# SCH_Test_2024-05-07.net
KiCad netlist of a schematic drawn in EasyEDA
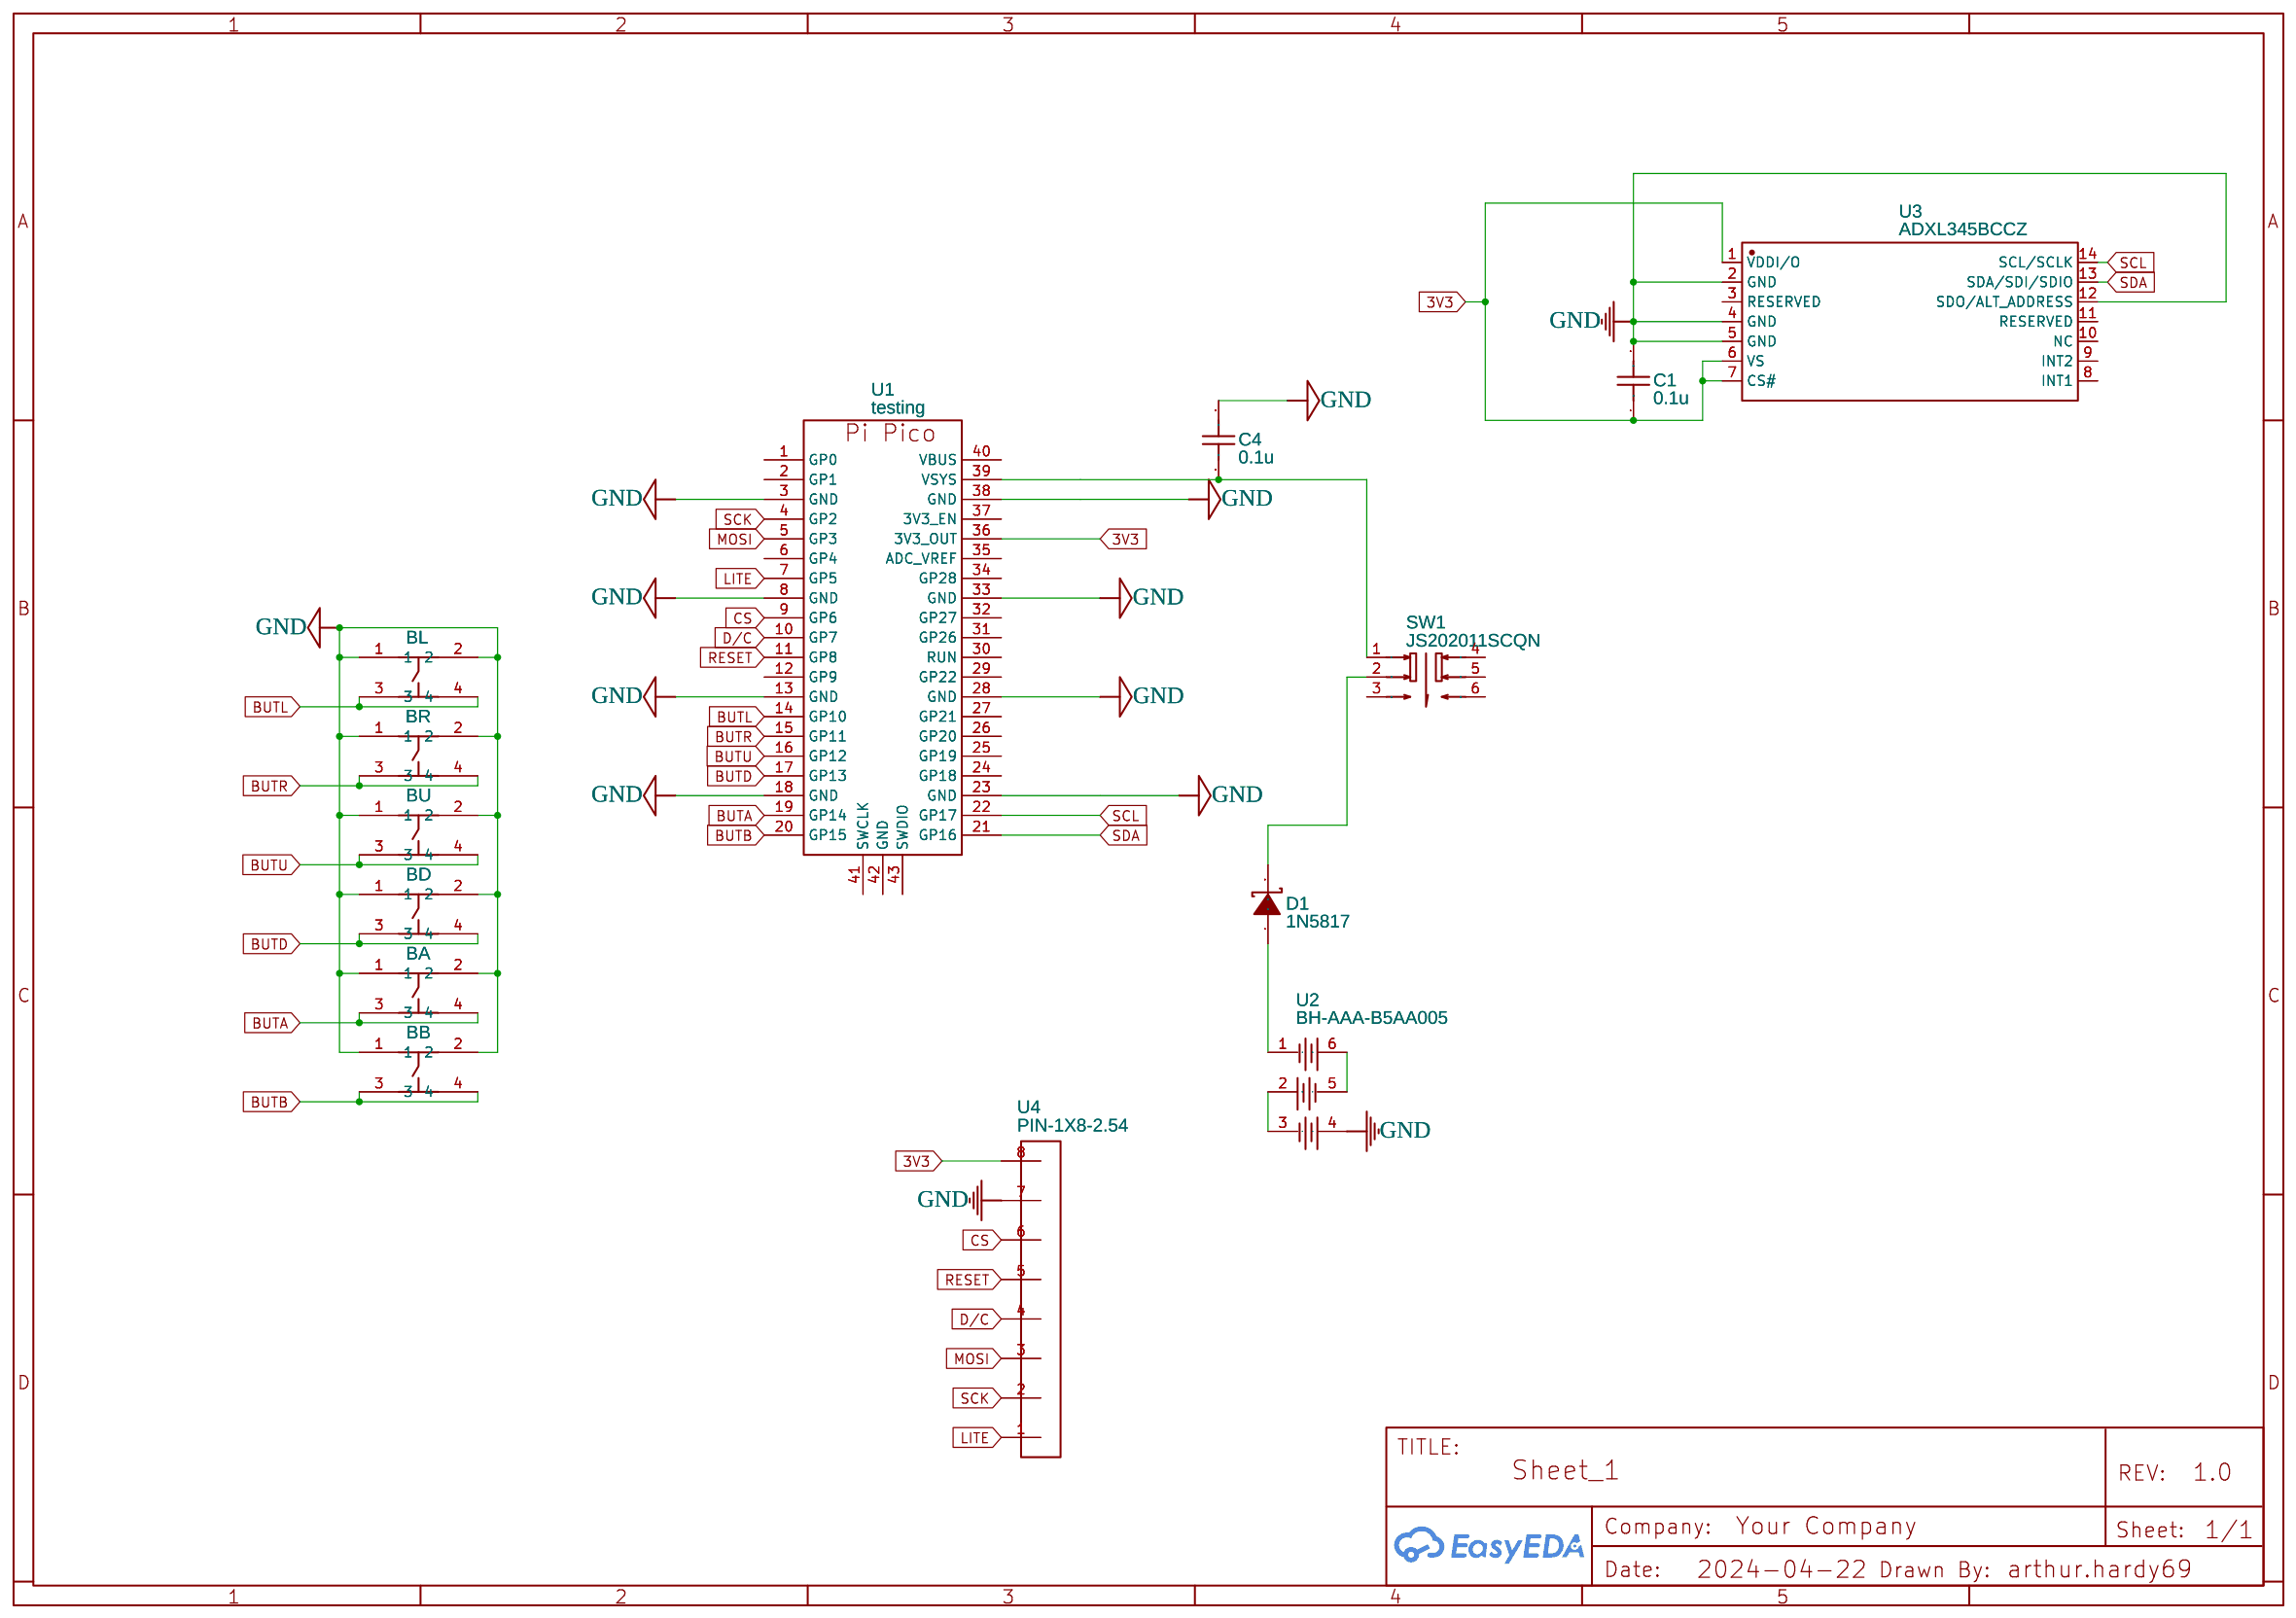
[diagram p0: schematic sheet]

(export (version "E")
  (design (tool "Eeschema 10.0.6"))
  (components
    (comp (ref "BA")
      (value "A")
      (fields (field (name "Manufacturer Part") "3101") (field (name "Manufacturer") "Adafruit"))
      (libsource (lib "") (part "Soft Tactile Button 8x8 (Adafruit 3101)_3"))
    )
    (comp (ref "BB")
      (value "B")
      (fields (field (name "Manufacturer Part") "3101") (field (name "Manufacturer") "Adafruit"))
      (libsource (lib "") (part "Soft Tactile Button 8x8 (Adafruit 3101)"))
    )
    (comp (ref "BD")
      (value "Down")
      (fields (field (name "Manufacturer Part") "3101") (field (name "Manufacturer") "Adafruit"))
      (libsource (lib "") (part "Soft Tactile Button 8x8 (Adafruit 3101)_2"))
    )
    (comp (ref "BL")
      (value "Left")
      (fields (field (name "Manufacturer Part") "3101") (field (name "Manufacturer") "Adafruit"))
      (libsource (lib "") (part "Soft Tactile Button 8x8 (Adafruit 3101)_1"))
    )
    (comp (ref "BR")
      (value "Right")
      (fields (field (name "Manufacturer Part") "3101") (field (name "Manufacturer") "Adafruit"))
      (libsource (lib "") (part "Soft Tactile Button 8x8 (Adafruit 3101)_5"))
    )
    (comp (ref "BU")
      (value "Up")
      (fields (field (name "Manufacturer Part") "3101") (field (name "Manufacturer") "Adafruit"))
      (libsource (lib "") (part "Soft Tactile Button 8x8 (Adafruit 3101)_4"))
    )
    (comp (ref "C1") (value "0.1u") (libsource (lib "") (part "C_0603_US")))
    (comp (ref "C4") (value "0.1u") (libsource (lib "") (part "C_0603_US")))
    (comp (ref "D1")
      (value "1N5817")
      (fields (field (name "Manufacturer") "MDD"))
      (libsource (lib "") (part "1N5817"))
    )
    (comp (ref "SW1")
      (value "JS202011SCQN")
      (fields (field (name "Manufacturer") "C&K"))
      (libsource (lib "") (part "JS202011SCQN"))
    )
    (comp (ref "U1")
      (value "testing")
      (fields
        (field (name "Manufacturer Part") "Pi Pico")
        (field (name "Manufacturer") "Raspberry Pi Foundation")
      )
      (libsource (lib "") (part "testing"))
    )
    (comp (ref "U2")
      (value "BH-AAA-B5AA005")
      (fields (field (name "Manufacturer") "MYOUNG(美阳)"))
      (libsource (lib "") (part "BH-AAA-B5AA005"))
    )
    (comp (ref "U3")
      (value "ADXL345BCCZ")
      (fields (field (name "Manufacturer") "ADI(亚德诺)"))
      (libsource (lib "") (part "ADXL345BCCZ"))
    )
    (comp (ref "U4") (value "PIN-1X8-2.54") (libsource (lib "") (part "PIN-1X8-2.54")))
  )
  (nets
    (net (code "1") (name "3V3") (class "Default")
      (node (ref "C1") (pin "1") (pinfunction "1_1") (pintype "unspecified"))
      (node (ref "U1") (pin "36") (pinfunction "3V3_OUT_36") (pintype "unspecified"))
      (node (ref "U3") (pin "1") (pinfunction "VDDI/O_1") (pintype "unspecified"))
      (node (ref "U3") (pin "6") (pinfunction "VS_6") (pintype "unspecified"))
      (node (ref "U3") (pin "7") (pinfunction "CS#_7") (pintype "unspecified"))
      (node (ref "U4") (pin "8") (pintype "unspecified"))
    )
    (net (code "2") (name "BUTA") (class "Default")
      (node (ref "BA") (pin "3") (pinfunction "3_3") (pintype "unspecified"))
      (node (ref "BA") (pin "4") (pinfunction "4_4") (pintype "unspecified"))
      (node (ref "U1") (pin "19") (pinfunction "GP14_19") (pintype "unspecified"))
    )
    (net (code "3") (name "BUTB") (class "Default")
      (node (ref "BB") (pin "3") (pinfunction "3_3") (pintype "unspecified"))
      (node (ref "BB") (pin "4") (pinfunction "4_4") (pintype "unspecified"))
      (node (ref "U1") (pin "20") (pinfunction "GP15_20") (pintype "unspecified"))
    )
    (net (code "4") (name "BUTD") (class "Default")
      (node (ref "BD") (pin "3") (pinfunction "3_3") (pintype "unspecified"))
      (node (ref "BD") (pin "4") (pinfunction "4_4") (pintype "unspecified"))
      (node (ref "U1") (pin "17") (pinfunction "GP13_17") (pintype "unspecified"))
    )
    (net (code "5") (name "BUTL") (class "Default")
      (node (ref "BL") (pin "3") (pinfunction "3_3") (pintype "unspecified"))
      (node (ref "BL") (pin "4") (pinfunction "4_4") (pintype "unspecified"))
      (node (ref "U1") (pin "14") (pinfunction "GP10_14") (pintype "unspecified"))
    )
    (net (code "6") (name "BUTR") (class "Default")
      (node (ref "BR") (pin "3") (pinfunction "3_3") (pintype "unspecified"))
      (node (ref "BR") (pin "4") (pinfunction "4_4") (pintype "unspecified"))
      (node (ref "U1") (pin "15") (pinfunction "GP11_15") (pintype "unspecified"))
    )
    (net (code "7") (name "BUTU") (class "Default")
      (node (ref "BU") (pin "3") (pinfunction "3_3") (pintype "unspecified"))
      (node (ref "BU") (pin "4") (pinfunction "4_4") (pintype "unspecified"))
      (node (ref "U1") (pin "16") (pinfunction "GP12_16") (pintype "unspecified"))
    )
    (net (code "8") (name "CS") (class "Default")
      (node (ref "U1") (pin "9") (pinfunction "GP6_9") (pintype "unspecified"))
      (node (ref "U4") (pin "6") (pintype "unspecified"))
    )
    (net (code "9") (name "D{slash}C") (class "Default")
      (node (ref "U1") (pin "10") (pinfunction "GP7_10") (pintype "unspecified"))
      (node (ref "U4") (pin "4") (pintype "unspecified"))
    )
    (net (code "10") (name "GND") (class "Default")
      (node (ref "BA") (pin "1") (pinfunction "1_1") (pintype "unspecified"))
      (node (ref "BA") (pin "2") (pinfunction "2_2") (pintype "unspecified"))
      (node (ref "BB") (pin "1") (pinfunction "1_1") (pintype "unspecified"))
      (node (ref "BB") (pin "2") (pinfunction "2_2") (pintype "unspecified"))
      (node (ref "BD") (pin "1") (pinfunction "1_1") (pintype "unspecified"))
      (node (ref "BD") (pin "2") (pinfunction "2_2") (pintype "unspecified"))
      (node (ref "BL") (pin "1") (pinfunction "1_1") (pintype "unspecified"))
      (node (ref "BL") (pin "2") (pinfunction "2_2") (pintype "unspecified"))
      (node (ref "BR") (pin "1") (pinfunction "1_1") (pintype "unspecified"))
      (node (ref "BR") (pin "2") (pinfunction "2_2") (pintype "unspecified"))
      (node (ref "BU") (pin "1") (pinfunction "1_1") (pintype "unspecified"))
      (node (ref "BU") (pin "2") (pinfunction "2_2") (pintype "unspecified"))
      (node (ref "C1") (pin "2") (pinfunction "2_2") (pintype "unspecified"))
      (node (ref "C4") (pin "2") (pinfunction "2_2") (pintype "unspecified"))
      (node (ref "U1") (pin "13") (pinfunction "GND_13") (pintype "unspecified"))
      (node (ref "U1") (pin "18") (pinfunction "GND_18") (pintype "unspecified"))
      (node (ref "U1") (pin "23") (pinfunction "GND_23") (pintype "unspecified"))
      (node (ref "U1") (pin "28") (pinfunction "GND_28") (pintype "unspecified"))
      (node (ref "U1") (pin "3") (pinfunction "GND_3") (pintype "unspecified"))
      (node (ref "U1") (pin "33") (pinfunction "GND_33") (pintype "unspecified"))
      (node (ref "U1") (pin "38") (pinfunction "GND_38") (pintype "unspecified"))
      (node (ref "U1") (pin "8") (pinfunction "GND_8") (pintype "unspecified"))
      (node (ref "U2") (pin "4") (pinfunction "+_4") (pintype "input"))
      (node (ref "U3") (pin "12") (pinfunction "SDO/ALT_ADDRESS_12") (pintype "unspecified"))
      (node (ref "U3") (pin "2") (pinfunction "GND_2") (pintype "unspecified"))
      (node (ref "U3") (pin "4") (pinfunction "GND_4") (pintype "unspecified"))
      (node (ref "U3") (pin "5") (pinfunction "GND_5") (pintype "unspecified"))
      (node (ref "U4") (pin "7") (pintype "unspecified"))
    )
    (net (code "11") (name "LITE") (class "Default")
      (node (ref "U1") (pin "7") (pinfunction "GP5_7") (pintype "unspecified"))
      (node (ref "U4") (pin "1") (pintype "unspecified"))
    )
    (net (code "12") (name "MOSI") (class "Default")
      (node (ref "U1") (pin "5") (pinfunction "GP3_5") (pintype "unspecified"))
      (node (ref "U4") (pin "3") (pintype "unspecified"))
    )
    (net (code "13") (name "Net-(D1-A)") (class "Default")
      (node (ref "D1") (pin "1") (pinfunction "A_1") (pintype "unspecified"))
      (node (ref "U2") (pin "1") (pinfunction "-_1") (pintype "input"))
    )
    (net (code "14") (name "Net-(D1-K)") (class "Default")
      (node (ref "D1") (pin "2") (pinfunction "K_2") (pintype "unspecified"))
      (node (ref "SW1") (pin "2") (pinfunction "2_2") (pintype "unspecified"))
    )
    (net (code "15") (name "Net-(U1-VSYS)") (class "Default")
      (node (ref "C4") (pin "1") (pinfunction "1_1") (pintype "unspecified"))
      (node (ref "SW1") (pin "1") (pinfunction "1_1") (pintype "unspecified"))
      (node (ref "U1") (pin "39") (pinfunction "VSYS_39") (pintype "unspecified"))
    )
    (net (code "16") (name "Net-(U2-+-Pad2)") (class "Default")
      (node (ref "U2") (pin "2") (pinfunction "+_2") (pintype "input"))
      (node (ref "U2") (pin "3") (pinfunction "-_3") (pintype "input"))
    )
    (net (code "17") (name "Net-(U2-+-Pad6)") (class "Default")
      (node (ref "U2") (pin "5") (pinfunction "-_5") (pintype "input"))
      (node (ref "U2") (pin "6") (pinfunction "+_6") (pintype "input"))
    )
    (net (code "18") (name "RESET") (class "Default")
      (node (ref "U1") (pin "11") (pinfunction "GP8_11") (pintype "unspecified"))
      (node (ref "U4") (pin "5") (pintype "unspecified"))
    )
    (net (code "19") (name "SCK") (class "Default")
      (node (ref "U1") (pin "4") (pinfunction "GP2_4") (pintype "unspecified"))
      (node (ref "U4") (pin "2") (pintype "unspecified"))
    )
    (net (code "20") (name "SCL") (class "Default")
      (node (ref "U1") (pin "22") (pinfunction "GP17_22") (pintype "unspecified"))
      (node (ref "U3") (pin "14") (pinfunction "SCL/SCLK_14") (pintype "unspecified"))
    )
    (net (code "21") (name "SDA") (class "Default")
      (node (ref "U1") (pin "21") (pinfunction "GP16_21") (pintype "unspecified"))
      (node (ref "U3") (pin "13") (pinfunction "SDA/SDI/SDIO_13") (pintype "unspecified"))
    )
    (net (code "22") (name "unconnected-(SW1-Pad3)") (class "Default")
      (node (ref "SW1") (pin "3") (pinfunction "3_3") (pintype "unspecified"))
    )
    (net (code "23") (name "unconnected-(SW1-Pad4)") (class "Default")
      (node (ref "SW1") (pin "4") (pinfunction "4_4") (pintype "unspecified"))
    )
    (net (code "24") (name "unconnected-(SW1-Pad5)") (class "Default")
      (node (ref "SW1") (pin "5") (pinfunction "5_5") (pintype "unspecified"))
    )
    (net (code "25") (name "unconnected-(SW1-Pad6)") (class "Default")
      (node (ref "SW1") (pin "6") (pinfunction "6_6") (pintype "unspecified"))
    )
    (net (code "26") (name "unconnected-(U1-3V3_EN-Pad37)") (class "Default")
      (node (ref "U1") (pin "37") (pinfunction "3V3_EN_37") (pintype "unspecified"))
    )
    (net (code "27") (name "unconnected-(U1-ADC_VREF-Pad35)") (class "Default")
      (node (ref "U1") (pin "35") (pinfunction "ADC_VREF_35") (pintype "unspecified"))
    )
    (net (code "28") (name "unconnected-(U1-GND-Pad42)") (class "Default")
      (node (ref "U1") (pin "42") (pinfunction "GND_42") (pintype "unspecified"))
    )
    (net (code "29") (name "unconnected-(U1-GP0-Pad1)") (class "Default")
      (node (ref "U1") (pin "1") (pinfunction "GP0_1") (pintype "unspecified"))
    )
    (net (code "30") (name "unconnected-(U1-GP1-Pad2)") (class "Default")
      (node (ref "U1") (pin "2") (pinfunction "GP1_2") (pintype "unspecified"))
    )
    (net (code "31") (name "unconnected-(U1-GP4-Pad6)") (class "Default")
      (node (ref "U1") (pin "6") (pinfunction "GP4_6") (pintype "unspecified"))
    )
    (net (code "32") (name "unconnected-(U1-GP9-Pad12)") (class "Default")
      (node (ref "U1") (pin "12") (pinfunction "GP9_12") (pintype "unspecified"))
    )
    (net (code "33") (name "unconnected-(U1-GP18-Pad24)") (class "Default")
      (node (ref "U1") (pin "24") (pinfunction "GP18_24") (pintype "unspecified"))
    )
    (net (code "34") (name "unconnected-(U1-GP19-Pad25)") (class "Default")
      (node (ref "U1") (pin "25") (pinfunction "GP19_25") (pintype "unspecified"))
    )
    (net (code "35") (name "unconnected-(U1-GP20-Pad26)") (class "Default")
      (node (ref "U1") (pin "26") (pinfunction "GP20_26") (pintype "unspecified"))
    )
    (net (code "36") (name "unconnected-(U1-GP21-Pad27)") (class "Default")
      (node (ref "U1") (pin "27") (pinfunction "GP21_27") (pintype "unspecified"))
    )
    (net (code "37") (name "unconnected-(U1-GP22-Pad29)") (class "Default")
      (node (ref "U1") (pin "29") (pinfunction "GP22_29") (pintype "unspecified"))
    )
    (net (code "38") (name "unconnected-(U1-GP26-Pad31)") (class "Default")
      (node (ref "U1") (pin "31") (pinfunction "GP26_31") (pintype "unspecified"))
    )
    (net (code "39") (name "unconnected-(U1-GP27-Pad32)") (class "Default")
      (node (ref "U1") (pin "32") (pinfunction "GP27_32") (pintype "unspecified"))
    )
    (net (code "40") (name "unconnected-(U1-GP28-Pad34)") (class "Default")
      (node (ref "U1") (pin "34") (pinfunction "GP28_34") (pintype "unspecified"))
    )
    (net (code "41") (name "unconnected-(U1-RUN-Pad30)") (class "Default")
      (node (ref "U1") (pin "30") (pinfunction "RUN_30") (pintype "unspecified"))
    )
    (net (code "42") (name "unconnected-(U1-SWCLK-Pad41)") (class "Default")
      (node (ref "U1") (pin "41") (pinfunction "SWCLK_41") (pintype "unspecified"))
    )
    (net (code "43") (name "unconnected-(U1-SWDIO-Pad43)") (class "Default")
      (node (ref "U1") (pin "43") (pinfunction "SWDIO_43") (pintype "unspecified"))
    )
    (net (code "44") (name "unconnected-(U1-VBUS-Pad40)") (class "Default")
      (node (ref "U1") (pin "40") (pinfunction "VBUS_40") (pintype "unspecified"))
    )
    (net (code "45") (name "unconnected-(U3-INT1-Pad8)") (class "Default")
      (node (ref "U3") (pin "8") (pinfunction "INT1_8") (pintype "unspecified"))
    )
    (net (code "46") (name "unconnected-(U3-INT2-Pad9)") (class "Default")
      (node (ref "U3") (pin "9") (pinfunction "INT2_9") (pintype "unspecified"))
    )
    (net (code "47") (name "unconnected-(U3-NC-Pad10)") (class "Default")
      (node (ref "U3") (pin "10") (pinfunction "NC_10") (pintype "unspecified"))
    )
    (net (code "48") (name "unconnected-(U3-RESERVED-Pad3)") (class "Default")
      (node (ref "U3") (pin "3") (pinfunction "RESERVED_3") (pintype "unspecified"))
    )
    (net (code "49") (name "unconnected-(U3-RESERVED-Pad11)") (class "Default")
      (node (ref "U3") (pin "11") (pinfunction "RESERVED_11") (pintype "unspecified"))
    )
  )
)
